# PT2272.net
KiCad netlist of a schematic drawn in Altium Designer
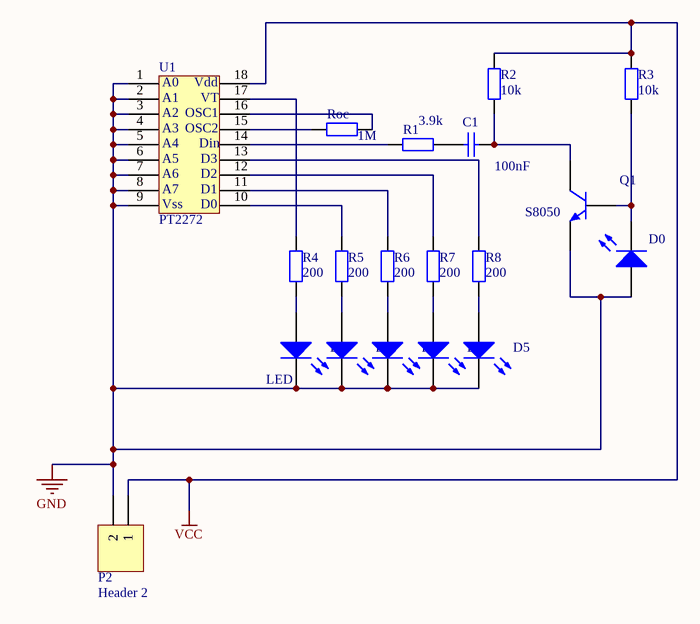
[diagram p0: PT2272.SchDoc]

(export (version "E")
  (design (tool "Eeschema 10.0.6"))
  (components
    (comp (ref "C1")
      (value "100nF")
      (footprint "CAP0.2")
      (description "Capacitor")
      (fields (field (name "Comment") "Cap") (field (name "PUBLISHER") "Altium Limited"))
      (libsource (lib "Miscellaneous Devices") (part "Cap"))
    )
    (comp (ref "D0")
      (value "~")
      (footprint "LEDLXH-3")
      (description "Typical INFRARED GaAs LED")
      (fields (field (name "PUBLISHER") "Altium Limited"))
      (libsource (lib "Miscellaneous Devices") (part "LED0"))
    )
    (comp (ref "D1")
      (value "LED")
      (footprint "LEDLXH-3")
      (description "Typical INFRARED GaAs LED")
      (fields (field (name "PUBLISHER") "Altium Limited"))
      (libsource (lib "Miscellaneous Devices") (part "LED0"))
    )
    (comp (ref "D2")
      (value "~")
      (footprint "LEDLXH-3")
      (description "Typical INFRARED GaAs LED")
      (fields (field (name "PUBLISHER") "Altium Limited"))
      (libsource (lib "Miscellaneous Devices") (part "LED0"))
    )
    (comp (ref "D3")
      (value "~")
      (footprint "LEDLXH-3")
      (description "Typical INFRARED GaAs LED")
      (fields (field (name "PUBLISHER") "Altium Limited"))
      (libsource (lib "Miscellaneous Devices") (part "LED0"))
    )
    (comp (ref "D4")
      (value "~")
      (footprint "LEDLXH-3")
      (description "Typical INFRARED GaAs LED")
      (fields (field (name "PUBLISHER") "Altium Limited"))
      (libsource (lib "Miscellaneous Devices") (part "LED0"))
    )
    (comp (ref "D5")
      (value "~")
      (footprint "LEDLXH-3")
      (description "Typical INFRARED GaAs LED")
      (fields (field (name "PUBLISHER") "Altium Limited"))
      (libsource (lib "Miscellaneous Devices") (part "LED0"))
    )
    (comp (ref "P2")
      (value "Header 2")
      (footprint "POWER PLUG2")
      (description "Header, 2-Pin")
      (fields (field (name "PUBLISHER") "Altium Limited"))
      (libsource (lib "Miscellaneous Connectors") (part "Header 2"))
    )
    (comp (ref "Q1")
      (value "S8050")
      (footprint "NPN-2")
      (description "NPN General Purpose Amplifier")
      (fields (field (name "PUBLISHER") "Altium Limited"))
      (libsource (lib "Miscellaneous Devices") (part "2N3904"))
    )
    (comp (ref "R1")
      (value "3.9k")
      (footprint "AXIAL-0.4")
      (description "Resistor")
      (fields (field (name "Comment") "Res2") (field (name "PUBLISHER") "Altium Limited"))
      (libsource (lib "") (part "Res2_1"))
    )
    (comp (ref "R2")
      (value "10k")
      (footprint "AXIAL-0.4")
      (description "Resistor")
      (fields (field (name "Comment") "Res2") (field (name "PUBLISHER") "Altium Limited"))
      (libsource (lib "Miscellaneous Devices") (part "Res2"))
    )
    (comp (ref "R3")
      (value "10k")
      (footprint "AXIAL-0.4")
      (description "Resistor")
      (fields (field (name "Comment") "Res2") (field (name "PUBLISHER") "Altium Limited"))
      (libsource (lib "Miscellaneous Devices") (part "Res2"))
    )
    (comp (ref "R4")
      (value "200")
      (footprint "AXIAL-0.4")
      (description "Resistor")
      (fields (field (name "Comment") "Res2") (field (name "PUBLISHER") "Altium Limited"))
      (libsource (lib "Miscellaneous Devices") (part "Res2"))
    )
    (comp (ref "R5")
      (value "200")
      (footprint "AXIAL-0.4")
      (description "Resistor")
      (fields (field (name "Comment") "Res2") (field (name "PUBLISHER") "Altium Limited"))
      (libsource (lib "Miscellaneous Devices") (part "Res2"))
    )
    (comp (ref "R6")
      (value "200")
      (footprint "AXIAL-0.4")
      (description "Resistor")
      (fields (field (name "Comment") "Res2") (field (name "PUBLISHER") "Altium Limited"))
      (libsource (lib "Miscellaneous Devices") (part "Res2"))
    )
    (comp (ref "R7")
      (value "200")
      (footprint "AXIAL-0.4")
      (description "Resistor")
      (fields (field (name "Comment") "Res2") (field (name "PUBLISHER") "Altium Limited"))
      (libsource (lib "Miscellaneous Devices") (part "Res2"))
    )
    (comp (ref "R8")
      (value "200")
      (footprint "AXIAL-0.4")
      (description "Resistor")
      (fields (field (name "Comment") "Res2") (field (name "PUBLISHER") "Altium Limited"))
      (libsource (lib "Miscellaneous Devices") (part "Res2"))
    )
    (comp (ref "Roc")
      (value "1M")
      (footprint "AXIAL-0.4")
      (description "Resistor")
      (fields (field (name "Comment") "Res2") (field (name "PUBLISHER") "Altium Limited"))
      (libsource (lib "") (part "Res2_1"))
    )
    (comp (ref "U1") (value "PT2272") (footprint "DIP-18") (libsource (lib "LixhSch") (part "PT2272")))
  )
  (nets
    (net (code "1") (name "GND") (class "Default")
      (node (ref "D0") (pin "1") (pinfunction "A_1") (pintype "passive"))
      (node (ref "D1") (pin "2") (pinfunction "K_2") (pintype "passive"))
      (node (ref "D2") (pin "2") (pinfunction "K_2") (pintype "passive"))
      (node (ref "D3") (pin "2") (pinfunction "K_2") (pintype "passive"))
      (node (ref "D4") (pin "2") (pinfunction "K_2") (pintype "passive"))
      (node (ref "D5") (pin "2") (pinfunction "K_2") (pintype "passive"))
      (node (ref "P2") (pin "2") (pinfunction "2_2") (pintype "passive"))
      (node (ref "Q1") (pin "1") (pinfunction "E_1") (pintype "passive"))
      (node (ref "U1") (pin "1") (pinfunction "1_1") (pintype "passive"))
      (node (ref "U1") (pin "2") (pinfunction "2_2") (pintype "passive"))
      (node (ref "U1") (pin "3") (pinfunction "3_3") (pintype "passive"))
      (node (ref "U1") (pin "4") (pinfunction "4_4") (pintype "passive"))
      (node (ref "U1") (pin "5") (pinfunction "5_5") (pintype "passive"))
      (node (ref "U1") (pin "6") (pinfunction "6_6") (pintype "passive"))
      (node (ref "U1") (pin "7") (pinfunction "7_7") (pintype "passive"))
      (node (ref "U1") (pin "8") (pinfunction "8_8") (pintype "passive"))
      (node (ref "U1") (pin "9") (pinfunction "9_9") (pintype "passive"))
    )
    (net (code "2") (name "Net-(C1-Pad1)") (class "Default")
      (node (ref "C1") (pin "1") (pinfunction "1_1") (pintype "passive"))
      (node (ref "R1") (pin "2") (pinfunction "2_2") (pintype "passive"))
    )
    (net (code "3") (name "Net-(D0-K)") (class "Default")
      (node (ref "D0") (pin "2") (pinfunction "K_2") (pintype "passive"))
      (node (ref "Q1") (pin "2") (pinfunction "B_2") (pintype "passive"))
      (node (ref "R3") (pin "1") (pinfunction "1_1") (pintype "passive"))
    )
    (net (code "4") (name "Net-(D1-A)") (class "Default")
      (node (ref "D1") (pin "1") (pinfunction "A_1") (pintype "passive"))
      (node (ref "R4") (pin "1") (pinfunction "1_1") (pintype "passive"))
    )
    (net (code "5") (name "Net-(D2-A)") (class "Default")
      (node (ref "D2") (pin "1") (pinfunction "A_1") (pintype "passive"))
      (node (ref "R5") (pin "1") (pinfunction "1_1") (pintype "passive"))
    )
    (net (code "6") (name "Net-(D3-A)") (class "Default")
      (node (ref "D3") (pin "1") (pinfunction "A_1") (pintype "passive"))
      (node (ref "R6") (pin "1") (pinfunction "1_1") (pintype "passive"))
    )
    (net (code "7") (name "Net-(D4-A)") (class "Default")
      (node (ref "D4") (pin "1") (pinfunction "A_1") (pintype "passive"))
      (node (ref "R7") (pin "1") (pinfunction "1_1") (pintype "passive"))
    )
    (net (code "8") (name "Net-(D5-A)") (class "Default")
      (node (ref "D5") (pin "1") (pinfunction "A_1") (pintype "passive"))
      (node (ref "R8") (pin "1") (pinfunction "1_1") (pintype "passive"))
    )
    (net (code "9") (name "Net-(Q1-C)") (class "Default")
      (node (ref "C1") (pin "2") (pinfunction "2_2") (pintype "passive"))
      (node (ref "Q1") (pin "3") (pinfunction "C_3") (pintype "passive"))
      (node (ref "R2") (pin "1") (pinfunction "1_1") (pintype "passive"))
    )
    (net (code "10") (name "Net-(R1-Pad1)") (class "Default")
      (node (ref "R1") (pin "1") (pinfunction "1_1") (pintype "passive"))
      (node (ref "U1") (pin "14") (pinfunction "14_14") (pintype "passive"))
    )
    (net (code "11") (name "Net-(R4-Pad2)") (class "Default")
      (node (ref "R4") (pin "2") (pinfunction "2_2") (pintype "passive"))
      (node (ref "U1") (pin "17") (pinfunction "17_17") (pintype "passive"))
    )
    (net (code "12") (name "Net-(R5-Pad2)") (class "Default")
      (node (ref "R5") (pin "2") (pinfunction "2_2") (pintype "passive"))
      (node (ref "U1") (pin "10") (pinfunction "10_10") (pintype "passive"))
    )
    (net (code "13") (name "Net-(R6-Pad2)") (class "Default")
      (node (ref "R6") (pin "2") (pinfunction "2_2") (pintype "passive"))
      (node (ref "U1") (pin "11") (pinfunction "11_11") (pintype "passive"))
    )
    (net (code "14") (name "Net-(R7-Pad2)") (class "Default")
      (node (ref "R7") (pin "2") (pinfunction "2_2") (pintype "passive"))
      (node (ref "U1") (pin "12") (pinfunction "12_12") (pintype "passive"))
    )
    (net (code "15") (name "Net-(R8-Pad2)") (class "Default")
      (node (ref "R8") (pin "2") (pinfunction "2_2") (pintype "passive"))
      (node (ref "U1") (pin "13") (pinfunction "13_13") (pintype "passive"))
    )
    (net (code "16") (name "Net-(Roc-Pad1)") (class "Default")
      (node (ref "Roc") (pin "1") (pinfunction "1_1") (pintype "passive"))
      (node (ref "U1") (pin "15") (pinfunction "15_15") (pintype "passive"))
    )
    (net (code "17") (name "Net-(Roc-Pad2)") (class "Default")
      (node (ref "Roc") (pin "2") (pinfunction "2_2") (pintype "passive"))
      (node (ref "U1") (pin "16") (pinfunction "16_16") (pintype "passive"))
    )
    (net (code "18") (name "VCC") (class "Default")
      (node (ref "P2") (pin "1") (pinfunction "1_1") (pintype "passive"))
      (node (ref "R2") (pin "2") (pinfunction "2_2") (pintype "passive"))
      (node (ref "R3") (pin "2") (pinfunction "2_2") (pintype "passive"))
      (node (ref "U1") (pin "18") (pinfunction "18_18") (pintype "passive"))
    )
  )
)
